# 3P_JST-XH_EXT.net
KiCad netlist of a schematic drawn in Altium Designer
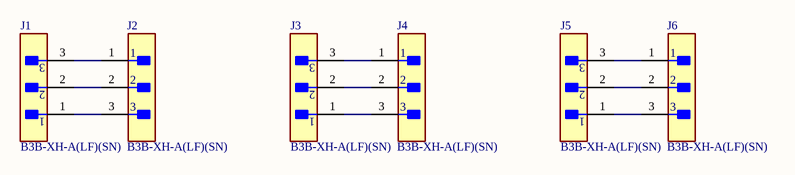
[diagram p0: 3P_JST-XH_EXT.SchDoc]

(export (version "E")
  (design (tool "Eeschema 10.0.6"))
  (components
    (comp (ref "J1")
      (value "B3B-XH-A(LF)(SN)")
      (footprint "FP-B3B-XH-A_LF_SN-MFG")
      (description "CONN HEADER VERT 3POS 2.5MM")
      (fields
        (field (name "OCTOPART") "https://octopart.com/b3b-xh-a%28lf%29%28sn%29-jst-3990185")
        (field (name "MANUFACTURER") "JST")
      )
      (libsource (lib "") (part "0d3f023dd272f625e17a2be33dea85f_1"))
    )
    (comp (ref "J2")
      (value "B3B-XH-A(LF)(SN)")
      (footprint "FP-B3B-XH-A_LF_SN-MFG")
      (description "CONN HEADER VERT 3POS 2.5MM")
      (fields
        (field (name "OCTOPART") "https://octopart.com/b3b-xh-a%28lf%29%28sn%29-jst-3990185")
        (field (name "MANUFACTURER") "JST")
      )
      (libsource (lib "Altium Content Vault") (part "0d3f023dd272f625e17a2be33dea85f"))
    )
    (comp (ref "J3")
      (value "B3B-XH-A(LF)(SN)")
      (footprint "FP-B3B-XH-A_LF_SN-MFG")
      (description "CONN HEADER VERT 3POS 2.5MM")
      (fields
        (field (name "OCTOPART") "https://octopart.com/b3b-xh-a%28lf%29%28sn%29-jst-3990185")
        (field (name "MANUFACTURER") "JST")
      )
      (libsource (lib "") (part "0d3f023dd272f625e17a2be33dea85f_1"))
    )
    (comp (ref "J4")
      (value "B3B-XH-A(LF)(SN)")
      (footprint "FP-B3B-XH-A_LF_SN-MFG")
      (description "CONN HEADER VERT 3POS 2.5MM")
      (fields
        (field (name "OCTOPART") "https://octopart.com/b3b-xh-a%28lf%29%28sn%29-jst-3990185")
        (field (name "MANUFACTURER") "JST")
      )
      (libsource (lib "Altium Content Vault") (part "0d3f023dd272f625e17a2be33dea85f"))
    )
    (comp (ref "J5")
      (value "B3B-XH-A(LF)(SN)")
      (footprint "FP-B3B-XH-A_LF_SN-MFG")
      (description "CONN HEADER VERT 3POS 2.5MM")
      (fields
        (field (name "OCTOPART") "https://octopart.com/b3b-xh-a%28lf%29%28sn%29-jst-3990185")
        (field (name "MANUFACTURER") "JST")
      )
      (libsource (lib "") (part "0d3f023dd272f625e17a2be33dea85f_1"))
    )
    (comp (ref "J6")
      (value "B3B-XH-A(LF)(SN)")
      (footprint "FP-B3B-XH-A_LF_SN-MFG")
      (description "CONN HEADER VERT 3POS 2.5MM")
      (fields
        (field (name "OCTOPART") "https://octopart.com/b3b-xh-a%28lf%29%28sn%29-jst-3990185")
        (field (name "MANUFACTURER") "JST")
      )
      (libsource (lib "Altium Content Vault") (part "0d3f023dd272f625e17a2be33dea85f"))
    )
  )
  (nets
    (net (code "1") (name "Net-(J1-Pad1)") (class "Default")
      (node (ref "J1") (pin "1") (pinfunction "1_1") (pintype "passive"))
      (node (ref "J2") (pin "3") (pinfunction "3_3") (pintype "passive"))
    )
    (net (code "2") (name "Net-(J1-Pad2)") (class "Default")
      (node (ref "J1") (pin "2") (pinfunction "2_2") (pintype "passive"))
      (node (ref "J2") (pin "2") (pinfunction "2_2") (pintype "passive"))
    )
    (net (code "3") (name "Net-(J1-Pad3)") (class "Default")
      (node (ref "J1") (pin "3") (pinfunction "3_3") (pintype "passive"))
      (node (ref "J2") (pin "1") (pinfunction "1_1") (pintype "passive"))
    )
    (net (code "4") (name "Net-(J3-Pad1)") (class "Default")
      (node (ref "J3") (pin "1") (pinfunction "1_1") (pintype "passive"))
      (node (ref "J4") (pin "3") (pinfunction "3_3") (pintype "passive"))
    )
    (net (code "5") (name "Net-(J3-Pad2)") (class "Default")
      (node (ref "J3") (pin "2") (pinfunction "2_2") (pintype "passive"))
      (node (ref "J4") (pin "2") (pinfunction "2_2") (pintype "passive"))
    )
    (net (code "6") (name "Net-(J3-Pad3)") (class "Default")
      (node (ref "J3") (pin "3") (pinfunction "3_3") (pintype "passive"))
      (node (ref "J4") (pin "1") (pinfunction "1_1") (pintype "passive"))
    )
    (net (code "7") (name "Net-(J5-Pad1)") (class "Default")
      (node (ref "J5") (pin "1") (pinfunction "1_1") (pintype "passive"))
      (node (ref "J6") (pin "3") (pinfunction "3_3") (pintype "passive"))
    )
    (net (code "8") (name "Net-(J5-Pad2)") (class "Default")
      (node (ref "J5") (pin "2") (pinfunction "2_2") (pintype "passive"))
      (node (ref "J6") (pin "2") (pinfunction "2_2") (pintype "passive"))
    )
    (net (code "9") (name "Net-(J5-Pad3)") (class "Default")
      (node (ref "J5") (pin "3") (pinfunction "3_3") (pintype "passive"))
      (node (ref "J6") (pin "1") (pinfunction "1_1") (pintype "passive"))
    )
  )
)
